# PSRR.net
KiCad netlist of a schematic drawn in Altium Designer
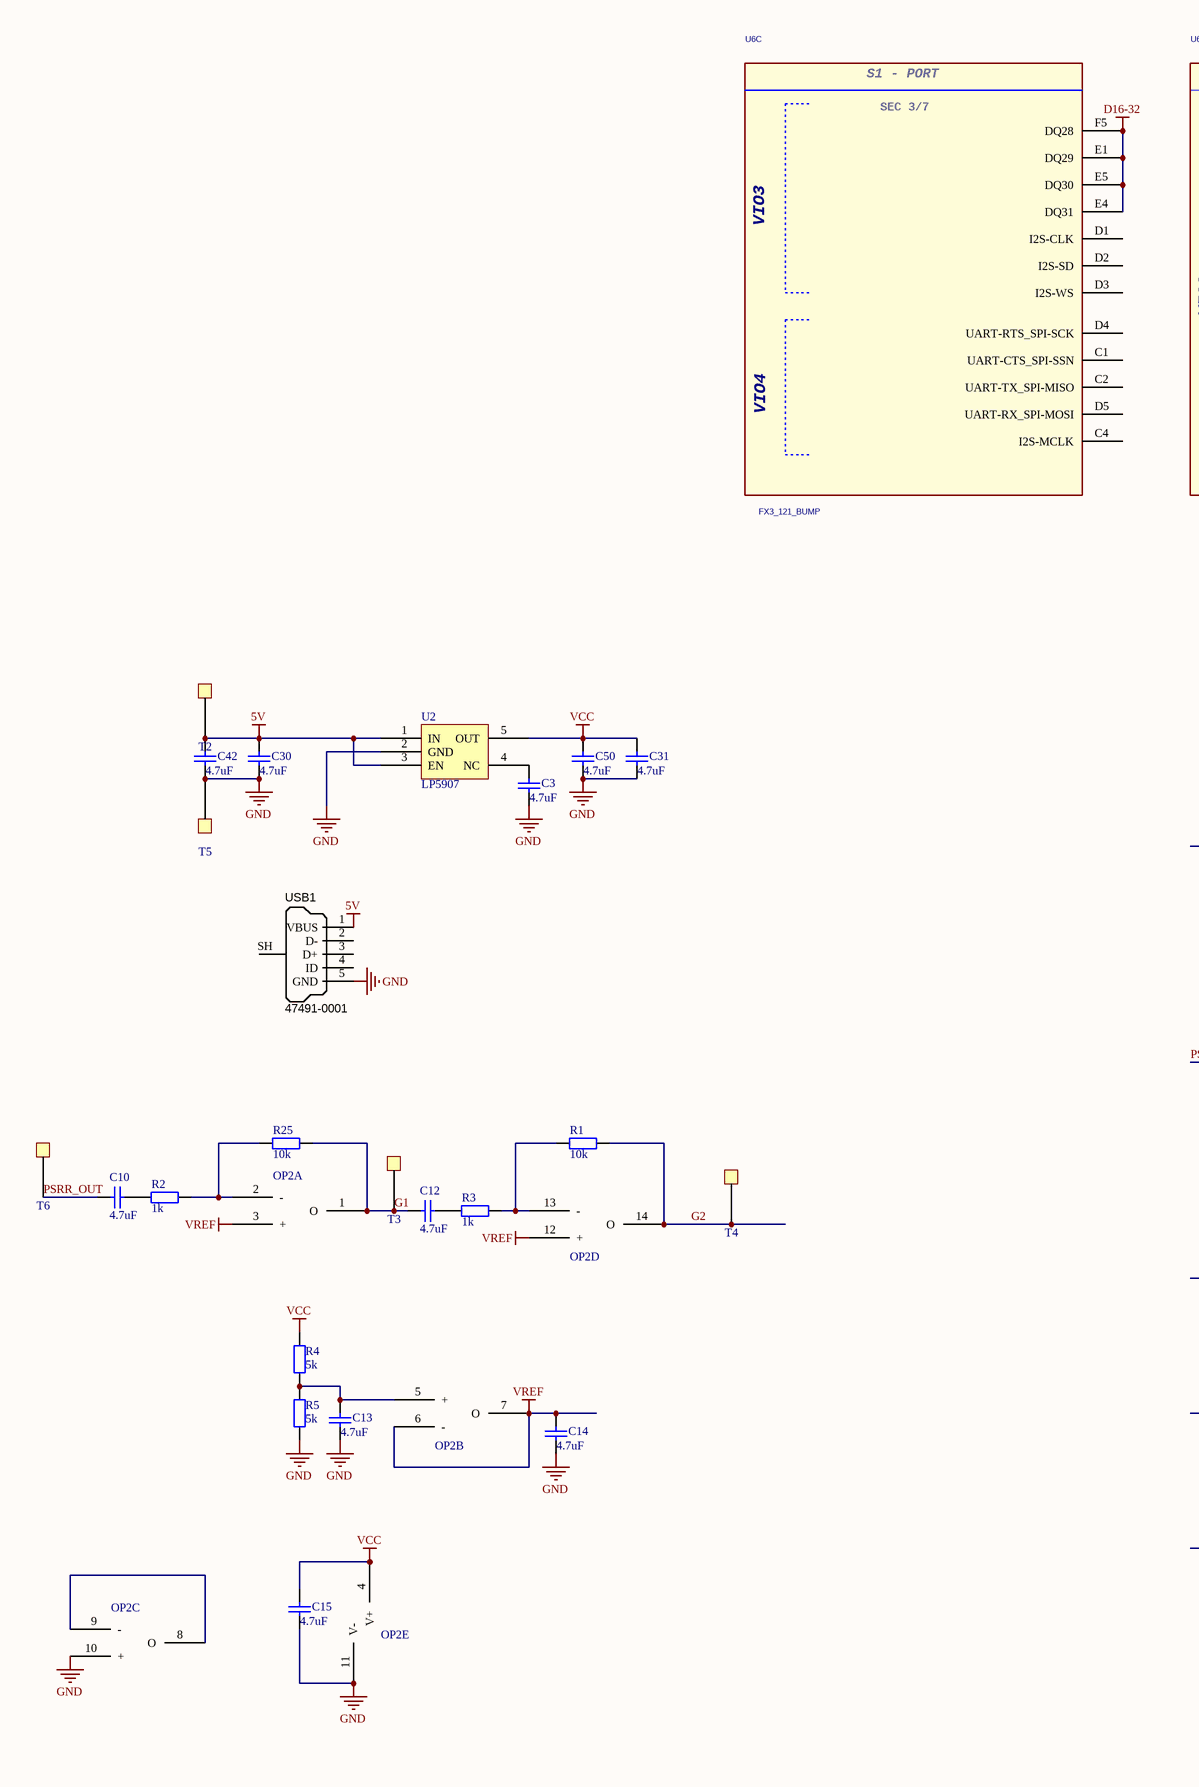
[diagram p0: PSRR.SchDoc, left]
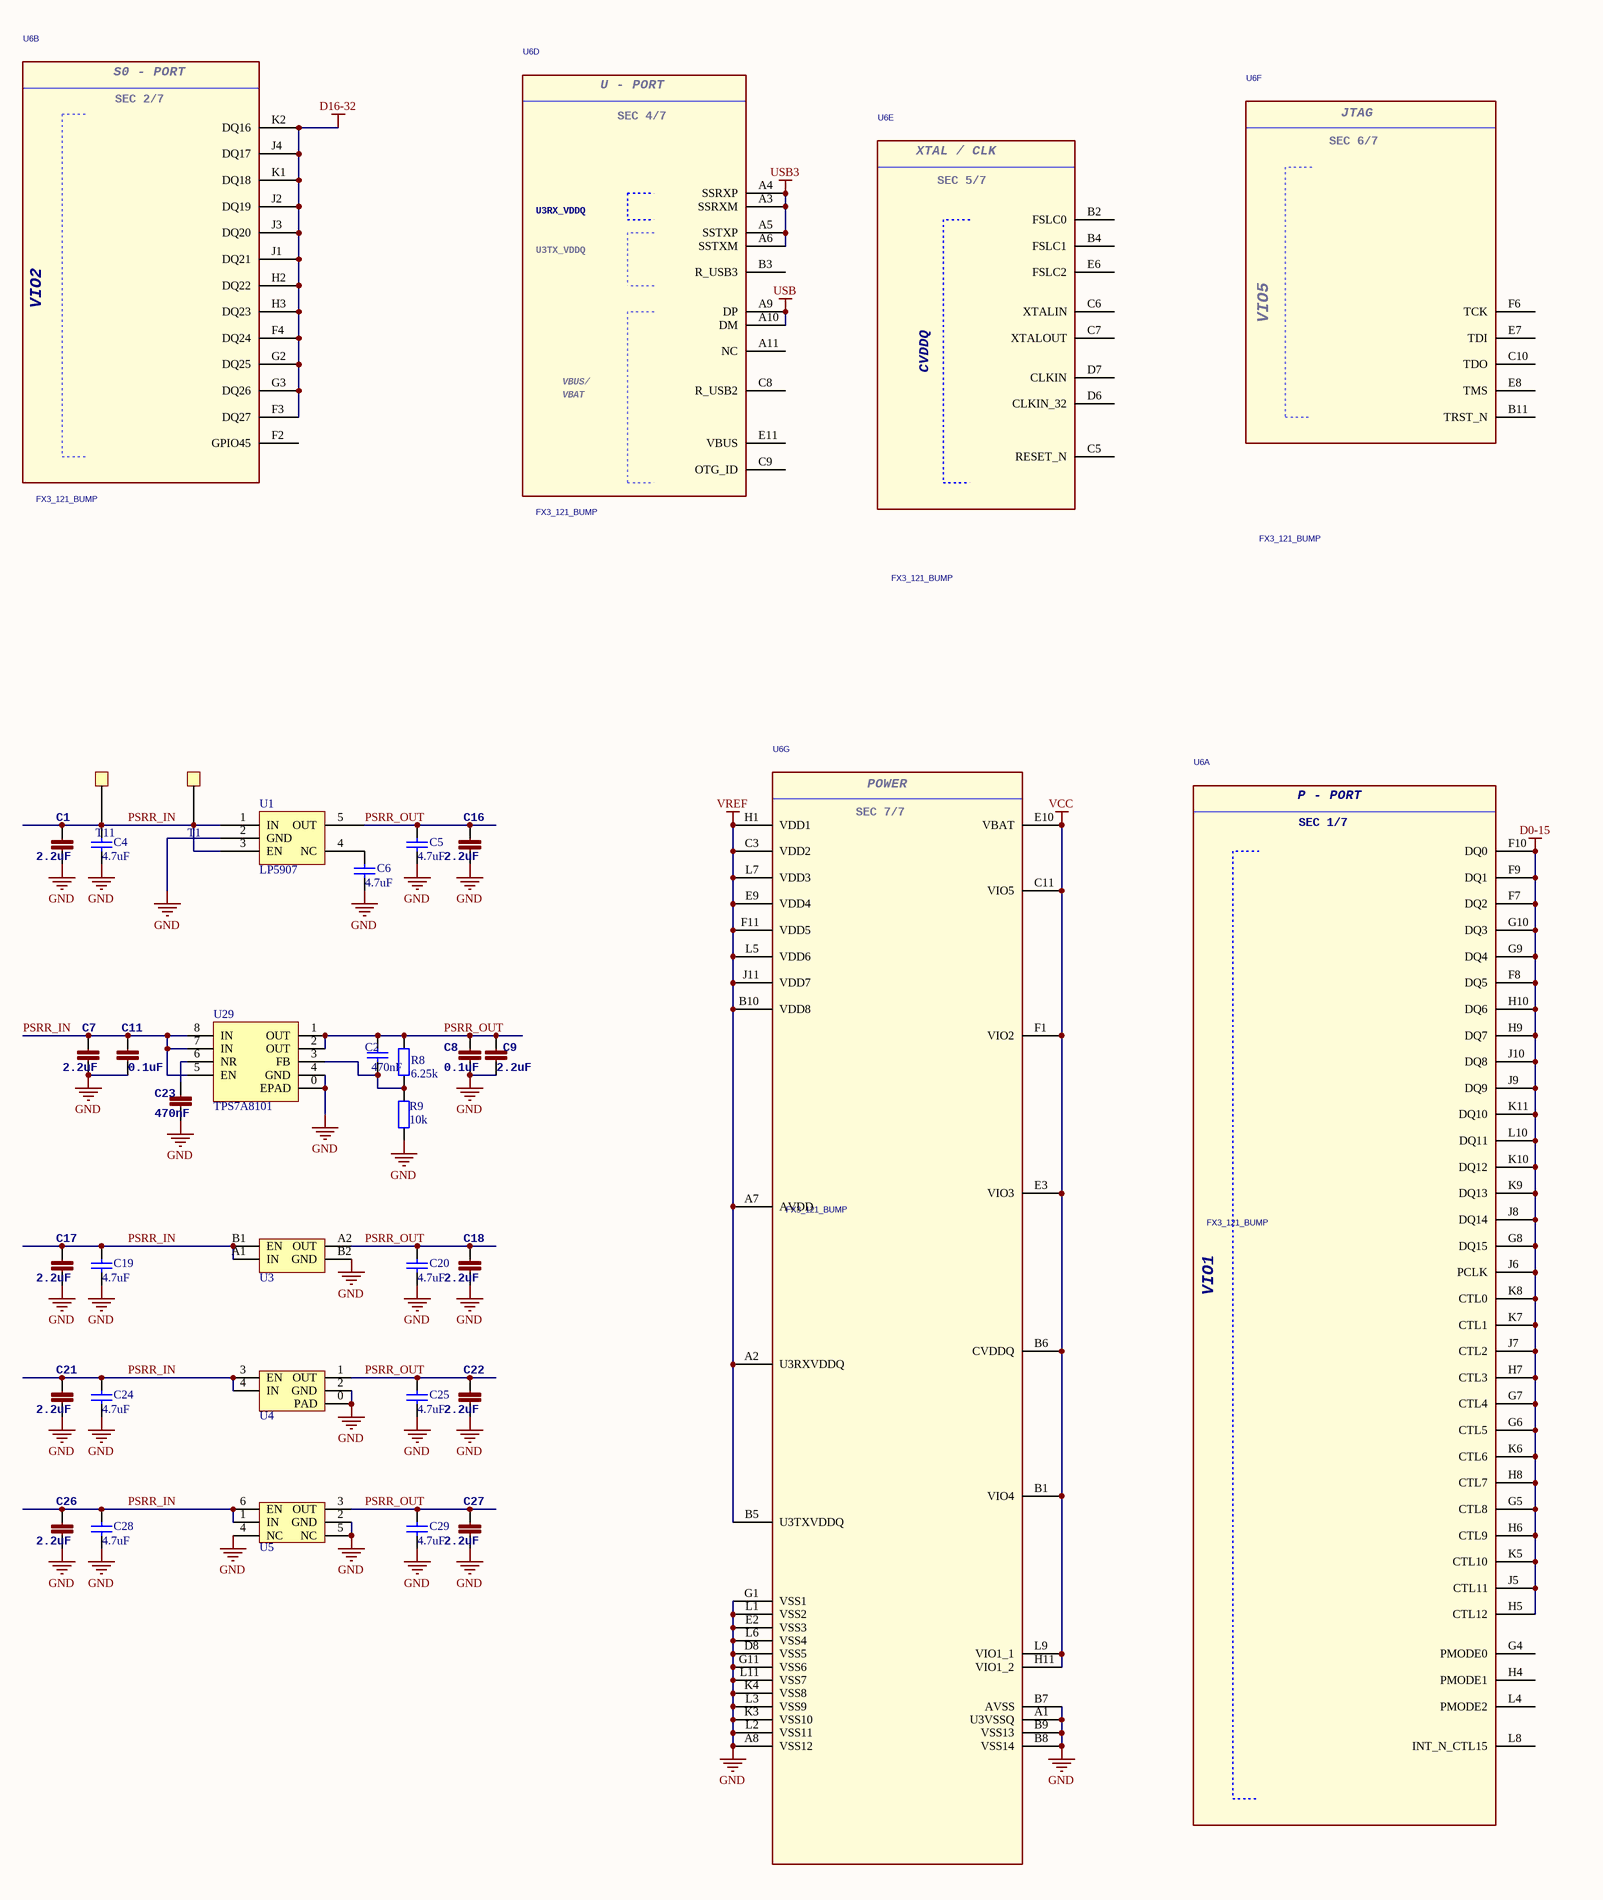
[diagram p1: PSRR.SchDoc, right]

(export (version "E")
  (design (tool "Eeschema 10.0.6"))
  (components
    (comp (ref "C1")
      (value "2.2uF")
      (footprint "0603")
      (description "<b>Capacitor</b>\nStandard 0603 ceramic capacitor, and 0.1\" leaded capacitor.")
      (fields (field (name "PARTNO") "CC0402ZRY5V7BB104"))
      (libsource (lib "pixhawk2") (part "CAP0402-CAP"))
    )
    (comp (ref "C2")
      (value "470nF")
      (footprint "0402")
      (description "Capacitor")
      (fields (field (name "PUBLISHER") "Altium Limited"))
      (libsource (lib "RTC6705") (part "Cap"))
    )
    (comp (ref "C3")
      (value "4.7uF")
      (footprint "0603")
      (description "Capacitor")
      (fields (field (name "PUBLISHER") "Altium Limited"))
      (libsource (lib "RTC6705") (part "Cap"))
    )
    (comp (ref "C4")
      (value "4.7uF")
      (footprint "0603")
      (description "Capacitor")
      (fields (field (name "PUBLISHER") "Altium Limited"))
      (libsource (lib "RTC6705") (part "Cap"))
    )
    (comp (ref "C5")
      (value "4.7uF")
      (footprint "0603")
      (description "Capacitor")
      (fields (field (name "PUBLISHER") "Altium Limited"))
      (libsource (lib "RTC6705") (part "Cap"))
    )
    (comp (ref "C6")
      (value "4.7uF")
      (footprint "0603")
      (description "Capacitor")
      (fields (field (name "PUBLISHER") "Altium Limited"))
      (libsource (lib "RTC6705") (part "Cap"))
    )
    (comp (ref "C7")
      (value "2.2uF")
      (footprint "0603")
      (description "<b>Capacitor</b>\nStandard 0603 ceramic capacitor, and 0.1\" leaded capacitor.")
      (fields (field (name "PARTNO") "CC0402ZRY5V7BB104"))
      (libsource (lib "pixhawk2") (part "CAP0402-CAP"))
    )
    (comp (ref "C8")
      (value "0.1uF")
      (footprint "0603")
      (description "<b>Capacitor</b>\nStandard 0603 ceramic capacitor, and 0.1\" leaded capacitor.")
      (fields (field (name "PARTNO") "CC0402ZRY5V7BB104"))
      (libsource (lib "*") (part "CAP0402-CAP"))
    )
    (comp (ref "C9")
      (value "2.2uF")
      (footprint "0603")
      (description "<b>Capacitor</b>\nStandard 0603 ceramic capacitor, and 0.1\" leaded capacitor.")
      (fields (field (name "PARTNO") "CC0402ZRY5V7BB104"))
      (libsource (lib "pixhawk2") (part "CAP0402-CAP"))
    )
    (comp (ref "C10")
      (value "4.7uF")
      (footprint "0603")
      (description "Capacitor")
      (fields (field (name "PUBLISHER") "Altium Limited"))
      (libsource (lib "RTC6705") (part "Cap"))
    )
    (comp (ref "C11")
      (value "0.1uF")
      (footprint "0402")
      (description "<b>Capacitor</b>\nStandard 0603 ceramic capacitor, and 0.1\" leaded capacitor.")
      (fields (field (name "PARTNO") "CC0402ZRY5V7BB104"))
      (libsource (lib "*") (part "CAP0402-CAP"))
    )
    (comp (ref "C12")
      (value "4.7uF")
      (footprint "0603")
      (description "Capacitor")
      (fields (field (name "PUBLISHER") "Altium Limited"))
      (libsource (lib "RTC6705") (part "Cap"))
    )
    (comp (ref "C13")
      (value "4.7uF")
      (footprint "0603")
      (description "Capacitor")
      (fields (field (name "PUBLISHER") "Altium Limited"))
      (libsource (lib "RTC6705") (part "Cap"))
    )
    (comp (ref "C14")
      (value "4.7uF")
      (footprint "0603")
      (description "Capacitor")
      (fields (field (name "PUBLISHER") "Altium Limited"))
      (libsource (lib "RTC6705") (part "Cap"))
    )
    (comp (ref "C15")
      (value "4.7uF")
      (footprint "0603")
      (description "Capacitor")
      (fields (field (name "PUBLISHER") "Altium Limited"))
      (libsource (lib "RTC6705") (part "Cap"))
    )
    (comp (ref "C16")
      (value "2.2uF")
      (footprint "0603")
      (description "<b>Capacitor</b>\nStandard 0603 ceramic capacitor, and 0.1\" leaded capacitor.")
      (fields (field (name "PARTNO") "CC0402ZRY5V7BB104"))
      (libsource (lib "pixhawk2") (part "CAP0402-CAP"))
    )
    (comp (ref "C17")
      (value "2.2uF")
      (footprint "0603")
      (description "<b>Capacitor</b>\nStandard 0603 ceramic capacitor, and 0.1\" leaded capacitor.")
      (fields (field (name "PARTNO") "CC0402ZRY5V7BB104"))
      (libsource (lib "pixhawk2") (part "CAP0402-CAP"))
    )
    (comp (ref "C18")
      (value "2.2uF")
      (footprint "0603")
      (description "<b>Capacitor</b>\nStandard 0603 ceramic capacitor, and 0.1\" leaded capacitor.")
      (fields (field (name "PARTNO") "CC0402ZRY5V7BB104"))
      (libsource (lib "pixhawk2") (part "CAP0402-CAP"))
    )
    (comp (ref "C19")
      (value "4.7uF")
      (footprint "0603")
      (description "Capacitor")
      (fields (field (name "PUBLISHER") "Altium Limited"))
      (libsource (lib "RTC6705") (part "Cap"))
    )
    (comp (ref "C20")
      (value "4.7uF")
      (footprint "0603")
      (description "Capacitor")
      (fields (field (name "PUBLISHER") "Altium Limited"))
      (libsource (lib "RTC6705") (part "Cap"))
    )
    (comp (ref "C21")
      (value "2.2uF")
      (footprint "0603")
      (description "<b>Capacitor</b>\nStandard 0603 ceramic capacitor, and 0.1\" leaded capacitor.")
      (fields (field (name "PARTNO") "CC0402ZRY5V7BB104"))
      (libsource (lib "pixhawk2") (part "CAP0402-CAP"))
    )
    (comp (ref "C22")
      (value "2.2uF")
      (footprint "0603")
      (description "<b>Capacitor</b>\nStandard 0603 ceramic capacitor, and 0.1\" leaded capacitor.")
      (fields (field (name "PARTNO") "CC0402ZRY5V7BB104"))
      (libsource (lib "pixhawk2") (part "CAP0402-CAP"))
    )
    (comp (ref "C23")
      (value "470nF")
      (footprint "0402")
      (description "<b>Capacitor</b>\nStandard 0603 ceramic capacitor, and 0.1\" leaded capacitor.")
      (fields (field (name "PARTNO") "CC0402ZRY5V7BB104"))
      (libsource (lib "*") (part "CAP0402-CAP"))
    )
    (comp (ref "C24")
      (value "4.7uF")
      (footprint "0603")
      (description "Capacitor")
      (fields (field (name "PUBLISHER") "Altium Limited"))
      (libsource (lib "RTC6705") (part "Cap"))
    )
    (comp (ref "C25")
      (value "4.7uF")
      (footprint "0603")
      (description "Capacitor")
      (fields (field (name "PUBLISHER") "Altium Limited"))
      (libsource (lib "RTC6705") (part "Cap"))
    )
    (comp (ref "C26")
      (value "2.2uF")
      (footprint "0402")
      (description "<b>Capacitor</b>\nStandard 0603 ceramic capacitor, and 0.1\" leaded capacitor.")
      (fields (field (name "PARTNO") "CC0402ZRY5V7BB104"))
      (libsource (lib "pixhawk2") (part "CAP0402-CAP"))
    )
    (comp (ref "C27")
      (value "2.2uF")
      (footprint "0402")
      (description "<b>Capacitor</b>\nStandard 0603 ceramic capacitor, and 0.1\" leaded capacitor.")
      (fields (field (name "PARTNO") "CC0402ZRY5V7BB104"))
      (libsource (lib "pixhawk2") (part "CAP0402-CAP"))
    )
    (comp (ref "C28")
      (value "4.7uF")
      (footprint "0402")
      (description "Capacitor")
      (fields (field (name "PUBLISHER") "Altium Limited"))
      (libsource (lib "RTC6705") (part "Cap"))
    )
    (comp (ref "C29")
      (value "4.7uF")
      (footprint "0402")
      (description "Capacitor")
      (fields (field (name "PUBLISHER") "Altium Limited"))
      (libsource (lib "RTC6705") (part "Cap"))
    )
    (comp (ref "C30")
      (value "4.7uF")
      (footprint "0603")
      (description "Capacitor")
      (fields (field (name "PUBLISHER") "Altium Limited"))
      (libsource (lib "RTC6705") (part "Cap"))
    )
    (comp (ref "C31")
      (value "4.7uF")
      (footprint "0603")
      (description "Capacitor")
      (fields (field (name "PUBLISHER") "Altium Limited"))
      (libsource (lib "RTC6705") (part "Cap"))
    )
    (comp (ref "C42")
      (value "4.7uF")
      (footprint "0603")
      (description "Capacitor")
      (fields (field (name "PUBLISHER") "Altium Limited"))
      (libsource (lib "RTC6705") (part "Cap"))
    )
    (comp (ref "C50")
      (value "4.7uF")
      (footprint "0603")
      (description "Capacitor")
      (fields (field (name "PUBLISHER") "Altium Limited"))
      (libsource (lib "RTC6705") (part "Cap"))
    )
    (comp (ref "OP2")
      (value "MCP6024")
      (footprint "TSSOP14_44MM_065P")
      (libsource (lib "schlib") (part "OP-SOP14"))
    )
    (comp (ref "R1")
      (value "10k")
      (footprint "0402")
      (description "Resistor")
      (fields (field (name "PUBLISHER") "Altium Limited"))
      (libsource (lib "Miscellaneous Devices") (part "Res2"))
    )
    (comp (ref "R2")
      (value "1k")
      (footprint "0402")
      (description "Resistor")
      (fields (field (name "PUBLISHER") "Altium Limited"))
      (libsource (lib "Miscellaneous Devices") (part "Res2"))
    )
    (comp (ref "R3")
      (value "1k")
      (footprint "0402")
      (description "Resistor")
      (fields (field (name "PUBLISHER") "Altium Limited"))
      (libsource (lib "Miscellaneous Devices") (part "Res2"))
    )
    (comp (ref "R4")
      (value "5k")
      (footprint "0402")
      (description "Resistor")
      (fields (field (name "PUBLISHER") "Altium Limited"))
      (libsource (lib "") (part "Res2_1"))
    )
    (comp (ref "R5")
      (value "5k")
      (footprint "0402")
      (description "Resistor")
      (fields (field (name "PUBLISHER") "Altium Limited"))
      (libsource (lib "") (part "Res2_1"))
    )
    (comp (ref "R8")
      (value "6.25k")
      (footprint "0402")
      (description "Resistor")
      (fields (field (name "PUBLISHER") "Altium Limited"))
      (libsource (lib "") (part "Res2_1"))
    )
    (comp (ref "R9")
      (value "10k")
      (footprint "0402")
      (description "Resistor")
      (fields (field (name "PUBLISHER") "Altium Limited"))
      (libsource (lib "") (part "Res2_1"))
    )
    (comp (ref "R25")
      (value "10k")
      (footprint "0402")
      (description "Resistor")
      (fields (field (name "PUBLISHER") "Altium Limited"))
      (libsource (lib "Miscellaneous Devices") (part "Res2"))
    )
    (comp (ref "T1") (value "TestPad") (footprint "TestPad") (libsource (lib "sch") (part "TestPad")))
    (comp (ref "T2") (value "TestPad") (footprint "TestPad") (libsource (lib "sch") (part "TestPad")))
    (comp (ref "T3") (value "TestPad") (footprint "TestPad") (libsource (lib "sch") (part "TestPad")))
    (comp (ref "T4") (value "TestPad") (footprint "TestPad") (libsource (lib "sch") (part "TestPad")))
    (comp (ref "T5") (value "TestPad") (footprint "TestPad") (libsource (lib "") (part "TestPad_1")))
    (comp (ref "T6") (value "TestPad") (footprint "TestPad") (libsource (lib "sch") (part "TestPad")))
    (comp (ref "T11") (value "TestPad") (footprint "TestPad") (libsource (lib "sch") (part "TestPad")))
    (comp (ref "U1") (value "LP5907") (footprint "SOT23-5") (libsource (lib "RTC6705") (part "LP5907")))
    (comp (ref "U2") (value "LP5907") (footprint "SOT23-5") (libsource (lib "RTC6705") (part "LP5907")))
    (comp (ref "U3") (value "LP5907-BGA") (footprint "DSBGA-4") (libsource (lib "sch") (part "LP5907-BGA")))
    (comp (ref "U4") (value "LP5907-X2SON") (footprint "X2SON") (libsource (lib "sch") (part "LP5907-X2SON")))
    (comp (ref "U5")
      (value "TLV700xx-WSON")
      (footprint "WSON")
      (libsource (lib "sch") (part "TLV700xx-WSON"))
    )
    (comp (ref "U6")
      (value "FX3_121_BUMP")
      (footprint "FX3_121_BUMP")
      (description "FX3")
      (fields (field (name "MANUFACTURER") "Cypress"))
      (libsource (lib "cyusb3014") (part "FX3_121_BUMP_10"))
    )
    (comp (ref "U29")
      (value "TPS7A8101")
      (footprint "TPS7A8101")
      (libsource (lib "F4SDR") (part "TPS7A8101"))
    )
    (comp (ref "USB1")
      (value "USB Micro Type B")
      (footprint "MICRO-YZX")
      (description "Connector SMD USB Micro Type B middle mount")
      (fields (field (name "MANUFACTURER PART NUMBER 1") "47491-0001"))
      (libsource (lib "PBL - Connectors") (part "USB_Micro_TypeB"))
    )
  )
  (nets
    (net (code "1") (name "/G1") (class "Default")
      (node (ref "C12") (pin "2") (pinfunction "2_2") (pintype "passive"))
      (node (ref "OP2") (pin "1") (pinfunction "O_1") (pintype "passive"))
      (node (ref "R25") (pin "2") (pinfunction "2_2") (pintype "passive"))
      (node (ref "T3") (pin "1") (pinfunction "3_1") (pintype "passive"))
    )
    (net (code "2") (name "/G2") (class "Default")
      (node (ref "OP2") (pin "14") (pinfunction "O_14") (pintype "passive"))
      (node (ref "R1") (pin "2") (pinfunction "2_2") (pintype "passive"))
      (node (ref "T4") (pin "1") (pinfunction "3_1") (pintype "passive"))
    )
    (net (code "3") (name "/PSRR_IN") (class "Default")
      (node (ref "C1") (pin "2") (pinfunction "2_2") (pintype "passive"))
      (node (ref "C11") (pin "2") (pinfunction "2_2") (pintype "passive"))
      (node (ref "C17") (pin "2") (pinfunction "2_2") (pintype "passive"))
      (node (ref "C19") (pin "2") (pinfunction "2_2") (pintype "passive"))
      (node (ref "C21") (pin "2") (pinfunction "2_2") (pintype "passive"))
      (node (ref "C24") (pin "2") (pinfunction "2_2") (pintype "passive"))
      (node (ref "C26") (pin "2") (pinfunction "2_2") (pintype "passive"))
      (node (ref "C28") (pin "2") (pinfunction "2_2") (pintype "passive"))
      (node (ref "C4") (pin "2") (pinfunction "2_2") (pintype "passive"))
      (node (ref "C7") (pin "2") (pinfunction "2_2") (pintype "passive"))
      (node (ref "T1") (pin "1") (pinfunction "3_1") (pintype "passive"))
      (node (ref "T11") (pin "1") (pinfunction "3_1") (pintype "passive"))
      (node (ref "U1") (pin "1") (pinfunction "IN_1") (pintype "passive"))
      (node (ref "U1") (pin "3") (pinfunction "EN_3") (pintype "passive"))
      (node (ref "U29") (pin "5") (pinfunction "EN_5") (pintype "passive"))
      (node (ref "U29") (pin "7") (pinfunction "IN_7") (pintype "passive"))
      (node (ref "U29") (pin "8") (pinfunction "IN_8") (pintype "passive"))
      (node (ref "U3") (pin "A1") (pinfunction "IN_A1") (pintype "passive"))
      (node (ref "U3") (pin "B1") (pinfunction "EN_B1") (pintype "passive"))
      (node (ref "U4") (pin "3") (pinfunction "EN_3") (pintype "passive"))
      (node (ref "U4") (pin "4") (pinfunction "IN_4") (pintype "passive"))
      (node (ref "U5") (pin "1") (pinfunction "IN_1") (pintype "passive"))
      (node (ref "U5") (pin "6") (pinfunction "EN_6") (pintype "passive"))
    )
    (net (code "4") (name "/PSRR_OUT") (class "Default")
      (node (ref "C10") (pin "2") (pinfunction "2_2") (pintype "passive"))
      (node (ref "C16") (pin "2") (pinfunction "2_2") (pintype "passive"))
      (node (ref "C18") (pin "2") (pinfunction "2_2") (pintype "passive"))
      (node (ref "C2") (pin "1") (pinfunction "1_1") (pintype "passive"))
      (node (ref "C20") (pin "2") (pinfunction "2_2") (pintype "passive"))
      (node (ref "C22") (pin "2") (pinfunction "2_2") (pintype "passive"))
      (node (ref "C25") (pin "2") (pinfunction "2_2") (pintype "passive"))
      (node (ref "C27") (pin "2") (pinfunction "2_2") (pintype "passive"))
      (node (ref "C29") (pin "2") (pinfunction "2_2") (pintype "passive"))
      (node (ref "C5") (pin "2") (pinfunction "2_2") (pintype "passive"))
      (node (ref "C8") (pin "2") (pinfunction "2_2") (pintype "passive"))
      (node (ref "C9") (pin "2") (pinfunction "2_2") (pintype "passive"))
      (node (ref "R8") (pin "1") (pinfunction "1_1") (pintype "passive"))
      (node (ref "T6") (pin "1") (pinfunction "3_1") (pintype "passive"))
      (node (ref "U1") (pin "5") (pinfunction "OUT_5") (pintype "passive"))
      (node (ref "U29") (pin "1") (pinfunction "OUT_1") (pintype "passive"))
      (node (ref "U29") (pin "2") (pinfunction "OUT_2") (pintype "passive"))
      (node (ref "U3") (pin "A2") (pinfunction "OUT_A2") (pintype "passive"))
      (node (ref "U4") (pin "1") (pinfunction "OUT_1") (pintype "passive"))
      (node (ref "U5") (pin "3") (pinfunction "OUT_3") (pintype "passive"))
    )
    (net (code "5") (name "5V") (class "Default")
      (node (ref "C30") (pin "2") (pinfunction "2_2") (pintype "passive"))
      (node (ref "C42") (pin "2") (pinfunction "2_2") (pintype "passive"))
      (node (ref "T2") (pin "1") (pinfunction "3_1") (pintype "passive"))
      (node (ref "U2") (pin "1") (pinfunction "IN_1") (pintype "passive"))
      (node (ref "U2") (pin "3") (pinfunction "EN_3") (pintype "passive"))
      (node (ref "USB1") (pin "1") (pinfunction "VBUS_1") (pintype "passive"))
    )
    (net (code "6") (name "D0-15") (class "Default")
      (node (ref "U6") (pin "F10") (pinfunction "DQ0_F10") (pintype "passive"))
      (node (ref "U6") (pin "F7") (pinfunction "DQ2_F7") (pintype "passive"))
      (node (ref "U6") (pin "F8") (pinfunction "DQ5_F8") (pintype "passive"))
      (node (ref "U6") (pin "F9") (pinfunction "DQ1_F9") (pintype "passive"))
      (node (ref "U6") (pin "G10") (pinfunction "DQ3_G10") (pintype "passive"))
      (node (ref "U6") (pin "G5") (pinfunction "CTL8_G5") (pintype "passive"))
      (node (ref "U6") (pin "G6") (pinfunction "CTL5_G6") (pintype "passive"))
      (node (ref "U6") (pin "G7") (pinfunction "CTL4_G7") (pintype "passive"))
      (node (ref "U6") (pin "G8") (pinfunction "DQ15_G8") (pintype "passive"))
      (node (ref "U6") (pin "G9") (pinfunction "DQ4_G9") (pintype "passive"))
      (node (ref "U6") (pin "H10") (pinfunction "DQ6_H10") (pintype "passive"))
      (node (ref "U6") (pin "H5") (pinfunction "CTL12_H5") (pintype "passive"))
      (node (ref "U6") (pin "H6") (pinfunction "CTL9_H6") (pintype "passive"))
      (node (ref "U6") (pin "H7") (pinfunction "CTL3_H7") (pintype "passive"))
      (node (ref "U6") (pin "H8") (pinfunction "CTL7_H8") (pintype "passive"))
      (node (ref "U6") (pin "H9") (pinfunction "DQ7_H9") (pintype "passive"))
      (node (ref "U6") (pin "J10") (pinfunction "DQ8_J10") (pintype "passive"))
      (node (ref "U6") (pin "J5") (pinfunction "CTL11_J5") (pintype "passive"))
      (node (ref "U6") (pin "J6") (pinfunction "PCLK_J6") (pintype "passive"))
      (node (ref "U6") (pin "J7") (pinfunction "CTL2_J7") (pintype "passive"))
      (node (ref "U6") (pin "J8") (pinfunction "DQ14_J8") (pintype "passive"))
      (node (ref "U6") (pin "J9") (pinfunction "DQ9_J9") (pintype "passive"))
      (node (ref "U6") (pin "K10") (pinfunction "DQ12_K10") (pintype "passive"))
      (node (ref "U6") (pin "K11") (pinfunction "DQ10_K11") (pintype "passive"))
      (node (ref "U6") (pin "K5") (pinfunction "CTL10_K5") (pintype "passive"))
      (node (ref "U6") (pin "K6") (pinfunction "CTL6_K6") (pintype "passive"))
      (node (ref "U6") (pin "K7") (pinfunction "CTL1_K7") (pintype "passive"))
      (node (ref "U6") (pin "K8") (pinfunction "CTL0_K8") (pintype "passive"))
      (node (ref "U6") (pin "K9") (pinfunction "DQ13_K9") (pintype "passive"))
      (node (ref "U6") (pin "L10") (pinfunction "DQ11_L10") (pintype "passive"))
    )
    (net (code "7") (name "D16-32") (class "Default")
      (node (ref "U6") (pin "E1") (pinfunction "DQ29_E1") (pintype "passive"))
      (node (ref "U6") (pin "E4") (pinfunction "DQ31_E4") (pintype "passive"))
      (node (ref "U6") (pin "E5") (pinfunction "DQ30_E5") (pintype "passive"))
      (node (ref "U6") (pin "F3") (pinfunction "DQ27_F3") (pintype "passive"))
      (node (ref "U6") (pin "F4") (pinfunction "DQ24_F4") (pintype "passive"))
      (node (ref "U6") (pin "F5") (pinfunction "DQ28_F5") (pintype "passive"))
      (node (ref "U6") (pin "G2") (pinfunction "DQ25_G2") (pintype "passive"))
      (node (ref "U6") (pin "G3") (pinfunction "DQ26_G3") (pintype "passive"))
      (node (ref "U6") (pin "H2") (pinfunction "DQ22_H2") (pintype "passive"))
      (node (ref "U6") (pin "H3") (pinfunction "DQ23_H3") (pintype "passive"))
      (node (ref "U6") (pin "J1") (pinfunction "DQ21_J1") (pintype "passive"))
      (node (ref "U6") (pin "J2") (pinfunction "DQ19_J2") (pintype "passive"))
      (node (ref "U6") (pin "J3") (pinfunction "DQ20_J3") (pintype "passive"))
      (node (ref "U6") (pin "J4") (pinfunction "DQ17_J4") (pintype "passive"))
      (node (ref "U6") (pin "K1") (pinfunction "DQ18_K1") (pintype "passive"))
      (node (ref "U6") (pin "K2") (pinfunction "DQ16_K2") (pintype "passive"))
    )
    (net (code "8") (name "GND") (class "Default")
      (node (ref "C1") (pin "1") (pinfunction "1_1") (pintype "passive"))
      (node (ref "C11") (pin "1") (pinfunction "1_1") (pintype "passive"))
      (node (ref "C13") (pin "1") (pinfunction "1_1") (pintype "passive"))
      (node (ref "C14") (pin "1") (pinfunction "1_1") (pintype "passive"))
      (node (ref "C15") (pin "1") (pinfunction "1_1") (pintype "passive"))
      (node (ref "C16") (pin "1") (pinfunction "1_1") (pintype "passive"))
      (node (ref "C17") (pin "1") (pinfunction "1_1") (pintype "passive"))
      (node (ref "C18") (pin "1") (pinfunction "1_1") (pintype "passive"))
      (node (ref "C19") (pin "1") (pinfunction "1_1") (pintype "passive"))
      (node (ref "C20") (pin "1") (pinfunction "1_1") (pintype "passive"))
      (node (ref "C21") (pin "1") (pinfunction "1_1") (pintype "passive"))
      (node (ref "C22") (pin "1") (pinfunction "1_1") (pintype "passive"))
      (node (ref "C23") (pin "1") (pinfunction "1_1") (pintype "passive"))
      (node (ref "C24") (pin "1") (pinfunction "1_1") (pintype "passive"))
      (node (ref "C25") (pin "1") (pinfunction "1_1") (pintype "passive"))
      (node (ref "C26") (pin "1") (pinfunction "1_1") (pintype "passive"))
      (node (ref "C27") (pin "1") (pinfunction "1_1") (pintype "passive"))
      (node (ref "C28") (pin "1") (pinfunction "1_1") (pintype "passive"))
      (node (ref "C29") (pin "1") (pinfunction "1_1") (pintype "passive"))
      (node (ref "C3") (pin "1") (pinfunction "1_1") (pintype "passive"))
      (node (ref "C30") (pin "1") (pinfunction "1_1") (pintype "passive"))
      (node (ref "C31") (pin "1") (pinfunction "1_1") (pintype "passive"))
      (node (ref "C4") (pin "1") (pinfunction "1_1") (pintype "passive"))
      (node (ref "C42") (pin "1") (pinfunction "1_1") (pintype "passive"))
      (node (ref "C5") (pin "1") (pinfunction "1_1") (pintype "passive"))
      (node (ref "C50") (pin "1") (pinfunction "1_1") (pintype "passive"))
      (node (ref "C6") (pin "1") (pinfunction "1_1") (pintype "passive"))
      (node (ref "C7") (pin "1") (pinfunction "1_1") (pintype "passive"))
      (node (ref "C8") (pin "1") (pinfunction "1_1") (pintype "passive"))
      (node (ref "C9") (pin "1") (pinfunction "1_1") (pintype "passive"))
      (node (ref "OP2") (pin "10") (pinfunction "+_10") (pintype "passive"))
      (node (ref "OP2") (pin "11") (pinfunction "V-_11") (pintype "passive"))
      (node (ref "R5") (pin "2") (pinfunction "2_2") (pintype "passive"))
      (node (ref "R9") (pin "2") (pinfunction "2_2") (pintype "passive"))
      (node (ref "T5") (pin "1") (pinfunction "3_1") (pintype "passive"))
      (node (ref "U1") (pin "2") (pinfunction "GND_2") (pintype "passive"))
      (node (ref "U2") (pin "2") (pinfunction "GND_2") (pintype "passive"))
      (node (ref "U29") (pin "0") (pinfunction "EPAD_0") (pintype "passive"))
      (node (ref "U29") (pin "4") (pinfunction "GND_4") (pintype "passive"))
      (node (ref "U3") (pin "B2") (pinfunction "GND_B2") (pintype "passive"))
      (node (ref "U4") (pin "0") (pinfunction "PAD_0") (pintype "passive"))
      (node (ref "U4") (pin "2") (pinfunction "GND_2") (pintype "passive"))
      (node (ref "U5") (pin "2") (pinfunction "GND_2") (pintype "passive"))
      (node (ref "U5") (pin "4") (pinfunction "NC_4") (pintype "passive"))
      (node (ref "U5") (pin "5") (pinfunction "NC_5") (pintype "passive"))
      (node (ref "U6") (pin "A1") (pinfunction "U3VSSQ_A1") (pintype "passive"))
      (node (ref "U6") (pin "A8") (pinfunction "VSS12_A8") (pintype "passive"))
      (node (ref "U6") (pin "B7") (pinfunction "AVSS_B7") (pintype "passive"))
      (node (ref "U6") (pin "B8") (pinfunction "VSS14_B8") (pintype "passive"))
      (node (ref "U6") (pin "B9") (pinfunction "VSS13_B9") (pintype "passive"))
      (node (ref "U6") (pin "D8") (pinfunction "VSS5_D8") (pintype "passive"))
      (node (ref "U6") (pin "E2") (pinfunction "VSS3_E2") (pintype "passive"))
      (node (ref "U6") (pin "G1") (pinfunction "VSS1_G1") (pintype "passive"))
      (node (ref "U6") (pin "G11") (pinfunction "VSS6_G11") (pintype "passive"))
      (node (ref "U6") (pin "K3") (pinfunction "VSS10_K3") (pintype "passive"))
      (node (ref "U6") (pin "K4") (pinfunction "VSS8_K4") (pintype "passive"))
      (node (ref "U6") (pin "L1") (pinfunction "VSS2_L1") (pintype "passive"))
      (node (ref "U6") (pin "L11") (pinfunction "VSS7_L11") (pintype "passive"))
      (node (ref "U6") (pin "L2") (pinfunction "VSS11_L2") (pintype "passive"))
      (node (ref "U6") (pin "L3") (pinfunction "VSS9_L3") (pintype "passive"))
      (node (ref "U6") (pin "L6") (pinfunction "VSS4_L6") (pintype "passive"))
      (node (ref "USB1") (pin "5") (pinfunction "GND_5") (pintype "passive"))
    )
    (net (code "9") (name "Net-(C10-Pad1)") (class "Default")
      (node (ref "C10") (pin "1") (pinfunction "1_1") (pintype "passive"))
      (node (ref "R2") (pin "1") (pinfunction "1_1") (pintype "passive"))
    )
    (net (code "10") (name "Net-(C12-Pad1)") (class "Default")
      (node (ref "C12") (pin "1") (pinfunction "1_1") (pintype "passive"))
      (node (ref "R3") (pin "1") (pinfunction "1_1") (pintype "passive"))
    )
    (net (code "11") (name "Net-(OP2A--)") (class "Default")
      (node (ref "OP2") (pin "2") (pinfunction "-_2") (pintype "passive"))
      (node (ref "R2") (pin "2") (pinfunction "2_2") (pintype "passive"))
      (node (ref "R25") (pin "1") (pinfunction "1_1") (pintype "passive"))
    )
    (net (code "12") (name "Net-(OP2B-+)") (class "Default")
      (node (ref "C13") (pin "2") (pinfunction "2_2") (pintype "passive"))
      (node (ref "OP2") (pin "5") (pinfunction "+_5") (pintype "passive"))
      (node (ref "R4") (pin "2") (pinfunction "2_2") (pintype "passive"))
      (node (ref "R5") (pin "1") (pinfunction "1_1") (pintype "passive"))
    )
    (net (code "13") (name "Net-(OP2C--)") (class "Default")
      (node (ref "OP2") (pin "8") (pinfunction "O_8") (pintype "passive"))
      (node (ref "OP2") (pin "9") (pinfunction "-_9") (pintype "passive"))
    )
    (net (code "14") (name "Net-(OP2D--)") (class "Default")
      (node (ref "OP2") (pin "13") (pinfunction "-_13") (pintype "passive"))
      (node (ref "R1") (pin "1") (pinfunction "1_1") (pintype "passive"))
      (node (ref "R3") (pin "2") (pinfunction "2_2") (pintype "passive"))
    )
    (net (code "15") (name "Net-(U1-NC)") (class "Default")
      (node (ref "C6") (pin "2") (pinfunction "2_2") (pintype "passive"))
      (node (ref "U1") (pin "4") (pinfunction "NC_4") (pintype "passive"))
    )
    (net (code "16") (name "Net-(U2-NC)") (class "Default")
      (node (ref "C3") (pin "2") (pinfunction "2_2") (pintype "passive"))
      (node (ref "U2") (pin "4") (pinfunction "NC_4") (pintype "passive"))
    )
    (net (code "17") (name "Net-(U29-FB)") (class "Default")
      (node (ref "C2") (pin "2") (pinfunction "2_2") (pintype "passive"))
      (node (ref "R8") (pin "2") (pinfunction "2_2") (pintype "passive"))
      (node (ref "R9") (pin "1") (pinfunction "1_1") (pintype "passive"))
      (node (ref "U29") (pin "3") (pinfunction "FB_3") (pintype "passive"))
    )
    (net (code "18") (name "Net-(U29-NR)") (class "Default")
      (node (ref "C23") (pin "2") (pinfunction "2_2") (pintype "passive"))
      (node (ref "U29") (pin "6") (pinfunction "NR_6") (pintype "passive"))
    )
    (net (code "19") (name "USB") (class "Default")
      (node (ref "U6") (pin "A10") (pinfunction "DM_A10") (pintype "passive"))
      (node (ref "U6") (pin "A9") (pinfunction "DP_A9") (pintype "passive"))
    )
    (net (code "20") (name "USB3") (class "Default")
      (node (ref "U6") (pin "A3") (pinfunction "SSRXM_A3") (pintype "passive"))
      (node (ref "U6") (pin "A4") (pinfunction "SSRXP_A4") (pintype "passive"))
      (node (ref "U6") (pin "A5") (pinfunction "SSTXP_A5") (pintype "passive"))
      (node (ref "U6") (pin "A6") (pinfunction "SSTXM_A6") (pintype "passive"))
    )
    (net (code "21") (name "VCC") (class "Default")
      (node (ref "C15") (pin "2") (pinfunction "2_2") (pintype "passive"))
      (node (ref "C31") (pin "2") (pinfunction "2_2") (pintype "passive"))
      (node (ref "C50") (pin "2") (pinfunction "2_2") (pintype "passive"))
      (node (ref "OP2") (pin "4") (pinfunction "V+_4") (pintype "passive"))
      (node (ref "R4") (pin "1") (pinfunction "1_1") (pintype "passive"))
      (node (ref "U2") (pin "5") (pinfunction "OUT_5") (pintype "passive"))
      (node (ref "U6") (pin "B1") (pinfunction "VIO4_B1") (pintype "passive"))
      (node (ref "U6") (pin "B6") (pinfunction "CVDDQ_B6") (pintype "passive"))
      (node (ref "U6") (pin "C11") (pinfunction "VIO5_C11") (pintype "passive"))
      (node (ref "U6") (pin "E10") (pinfunction "VBAT_E10") (pintype "passive"))
      (node (ref "U6") (pin "E3") (pinfunction "VIO3_E3") (pintype "passive"))
      (node (ref "U6") (pin "F1") (pinfunction "VIO2_F1") (pintype "passive"))
      (node (ref "U6") (pin "H11") (pinfunction "VIO1_2_H11") (pintype "passive"))
      (node (ref "U6") (pin "L9") (pinfunction "VIO1_1_L9") (pintype "passive"))
    )
    (net (code "22") (name "VREF") (class "Default")
      (node (ref "C14") (pin "2") (pinfunction "2_2") (pintype "passive"))
      (node (ref "OP2") (pin "12") (pinfunction "+_12") (pintype "passive"))
      (node (ref "OP2") (pin "3") (pinfunction "+_3") (pintype "passive"))
      (node (ref "OP2") (pin "6") (pinfunction "-_6") (pintype "passive"))
      (node (ref "OP2") (pin "7") (pinfunction "O_7") (pintype "passive"))
      (node (ref "U6") (pin "A2") (pinfunction "U3RXVDDQ_A2") (pintype "passive"))
      (node (ref "U6") (pin "A7") (pinfunction "AVDD_A7") (pintype "passive"))
      (node (ref "U6") (pin "B10") (pinfunction "VDD8_B10") (pintype "passive"))
      (node (ref "U6") (pin "B5") (pinfunction "U3TXVDDQ_B5") (pintype "passive"))
      (node (ref "U6") (pin "C3") (pinfunction "VDD2_C3") (pintype "passive"))
      (node (ref "U6") (pin "E9") (pinfunction "VDD4_E9") (pintype "passive"))
      (node (ref "U6") (pin "F11") (pinfunction "VDD5_F11") (pintype "passive"))
      (node (ref "U6") (pin "H1") (pinfunction "VDD1_H1") (pintype "passive"))
      (node (ref "U6") (pin "J11") (pinfunction "VDD7_J11") (pintype "passive"))
      (node (ref "U6") (pin "L5") (pinfunction "VDD6_L5") (pintype "passive"))
      (node (ref "U6") (pin "L7") (pinfunction "VDD3_L7") (pintype "passive"))
    )
    (net (code "23") (name "unconnected-(U6A-INT_N_CTL15-PadL8)") (class "Default")
      (node (ref "U6") (pin "L8") (pinfunction "INT_N_CTL15_L8") (pintype "passive"))
    )
    (net (code "24") (name "unconnected-(U6A-PMODE0-PadG4)") (class "Default")
      (node (ref "U6") (pin "G4") (pinfunction "PMODE0_G4") (pintype "passive"))
    )
    (net (code "25") (name "unconnected-(U6A-PMODE1-PadH4)") (class "Default")
      (node (ref "U6") (pin "H4") (pinfunction "PMODE1_H4") (pintype "passive"))
    )
    (net (code "26") (name "unconnected-(U6A-PMODE2-PadL4)") (class "Default")
      (node (ref "U6") (pin "L4") (pinfunction "PMODE2_L4") (pintype "passive"))
    )
    (net (code "27") (name "unconnected-(U6B-GPIO45-PadF2)") (class "Default")
      (node (ref "U6") (pin "F2") (pinfunction "GPIO45_F2") (pintype "passive"))
    )
    (net (code "28") (name "unconnected-(U6C-I2S-CLK-PadD1)") (class "Default")
      (node (ref "U6") (pin "D1") (pinfunction "I2S-CLK_D1") (pintype "passive"))
    )
    (net (code "29") (name "unconnected-(U6C-I2S-MCLK-PadC4)") (class "Default")
      (node (ref "U6") (pin "C4") (pinfunction "I2S-MCLK_C4") (pintype "passive"))
    )
    (net (code "30") (name "unconnected-(U6C-I2S-SD-PadD2)") (class "Default")
      (node (ref "U6") (pin "D2") (pinfunction "I2S-SD_D2") (pintype "passive"))
    )
    (net (code "31") (name "unconnected-(U6C-I2S-WS-PadD3)") (class "Default")
      (node (ref "U6") (pin "D3") (pinfunction "I2S-WS_D3") (pintype "passive"))
    )
    (net (code "32") (name "unconnected-(U6C-UART-CTS_SPI-SSN-PadC1)") (class "Default")
      (node (ref "U6") (pin "C1") (pinfunction "UART-CTS_SPI-SSN_C1") (pintype "passive"))
    )
    (net (code "33") (name "unconnected-(U6C-UART-RTS_SPI-SCK-PadD4)") (class "Default")
      (node (ref "U6") (pin "D4") (pinfunction "UART-RTS_SPI-SCK_D4") (pintype "passive"))
    )
    (net (code "34") (name "unconnected-(U6C-UART-RX_SPI-MOSI-PadD5)") (class "Default")
      (node (ref "U6") (pin "D5") (pinfunction "UART-RX_SPI-MOSI_D5") (pintype "passive"))
    )
    (net (code "35") (name "unconnected-(U6C-UART-TX_SPI-MISO-PadC2)") (class "Default")
      (node (ref "U6") (pin "C2") (pinfunction "UART-TX_SPI-MISO_C2") (pintype "passive"))
    )
    (net (code "36") (name "unconnected-(U6D-NC-PadA11)") (class "Default")
      (node (ref "U6") (pin "A11") (pinfunction "NC_A11") (pintype "passive"))
    )
    (net (code "37") (name "unconnected-(U6D-OTG_ID-PadC9)") (class "Default")
      (node (ref "U6") (pin "C9") (pinfunction "OTG_ID_C9") (pintype "passive"))
    )
    (net (code "38") (name "unconnected-(U6D-R_USB2-PadC8)") (class "Default")
      (node (ref "U6") (pin "C8") (pinfunction "R_USB2_C8") (pintype "passive"))
    )
    (net (code "39") (name "unconnected-(U6D-R_USB3-PadB3)") (class "Default")
      (node (ref "U6") (pin "B3") (pinfunction "R_USB3_B3") (pintype "passive"))
    )
    (net (code "40") (name "unconnected-(U6D-VBUS-PadE11)") (class "Default")
      (node (ref "U6") (pin "E11") (pinfunction "VBUS_E11") (pintype "passive"))
    )
    (net (code "41") (name "unconnected-(U6E-CLKIN-PadD7)") (class "Default")
      (node (ref "U6") (pin "D7") (pinfunction "CLKIN_D7") (pintype "passive"))
    )
    (net (code "42") (name "unconnected-(U6E-CLKIN_32-PadD6)") (class "Default")
      (node (ref "U6") (pin "D6") (pinfunction "CLKIN_32_D6") (pintype "passive"))
    )
    (net (code "43") (name "unconnected-(U6E-FSLC0-PadB2)") (class "Default")
      (node (ref "U6") (pin "B2") (pinfunction "FSLC0_B2") (pintype "passive"))
    )
    (net (code "44") (name "unconnected-(U6E-FSLC1-PadB4)") (class "Default")
      (node (ref "U6") (pin "B4") (pinfunction "FSLC1_B4") (pintype "passive"))
    )
    (net (code "45") (name "unconnected-(U6E-FSLC2-PadE6)") (class "Default")
      (node (ref "U6") (pin "E6") (pinfunction "FSLC2_E6") (pintype "passive"))
    )
    (net (code "46") (name "unconnected-(U6E-RESET_N-PadC5)") (class "Default")
      (node (ref "U6") (pin "C5") (pinfunction "RESET_N_C5") (pintype "passive"))
    )
    (net (code "47") (name "unconnected-(U6E-XTALIN-PadC6)") (class "Default")
      (node (ref "U6") (pin "C6") (pinfunction "XTALIN_C6") (pintype "passive"))
    )
    (net (code "48") (name "unconnected-(U6E-XTALOUT-PadC7)") (class "Default")
      (node (ref "U6") (pin "C7") (pinfunction "XTALOUT_C7") (pintype "passive"))
    )
    (net (code "49") (name "unconnected-(U6F-TCK-PadF6)") (class "Default")
      (node (ref "U6") (pin "F6") (pinfunction "TCK_F6") (pintype "passive"))
    )
    (net (code "50") (name "unconnected-(U6F-TDI-PadE7)") (class "Default")
      (node (ref "U6") (pin "E7") (pinfunction "TDI_E7") (pintype "passive"))
    )
    (net (code "51") (name "unconnected-(U6F-TDO-PadC10)") (class "Default")
      (node (ref "U6") (pin "C10") (pinfunction "TDO_C10") (pintype "passive"))
    )
    (net (code "52") (name "unconnected-(U6F-TMS-PadE8)") (class "Default")
      (node (ref "U6") (pin "E8") (pinfunction "TMS_E8") (pintype "passive"))
    )
    (net (code "53") (name "unconnected-(U6F-TRST_N-PadB11)") (class "Default")
      (node (ref "U6") (pin "B11") (pinfunction "TRST_N_B11") (pintype "passive"))
    )
    (net (code "54") (name "unconnected-(USB1-D+-Pad3)") (class "Default")
      (node (ref "USB1") (pin "3") (pinfunction "D+_3") (pintype "passive"))
    )
    (net (code "55") (name "unconnected-(USB1-D--Pad2)") (class "Default")
      (node (ref "USB1") (pin "2") (pinfunction "D-_2") (pintype "passive"))
    )
    (net (code "56") (name "unconnected-(USB1-ID-Pad4)") (class "Default")
      (node (ref "USB1") (pin "4") (pinfunction "ID_4") (pintype "passive"))
    )
    (net (code "57") (name "unconnected-(USB1-Shell-PadSH)") (class "Default")
      (node (ref "USB1") (pin "SH") (pinfunction "Shell_SH") (pintype "passive"))
    )
  )
)
